# LASERTAG.net
KiCad netlist of a schematic drawn in EAGLE
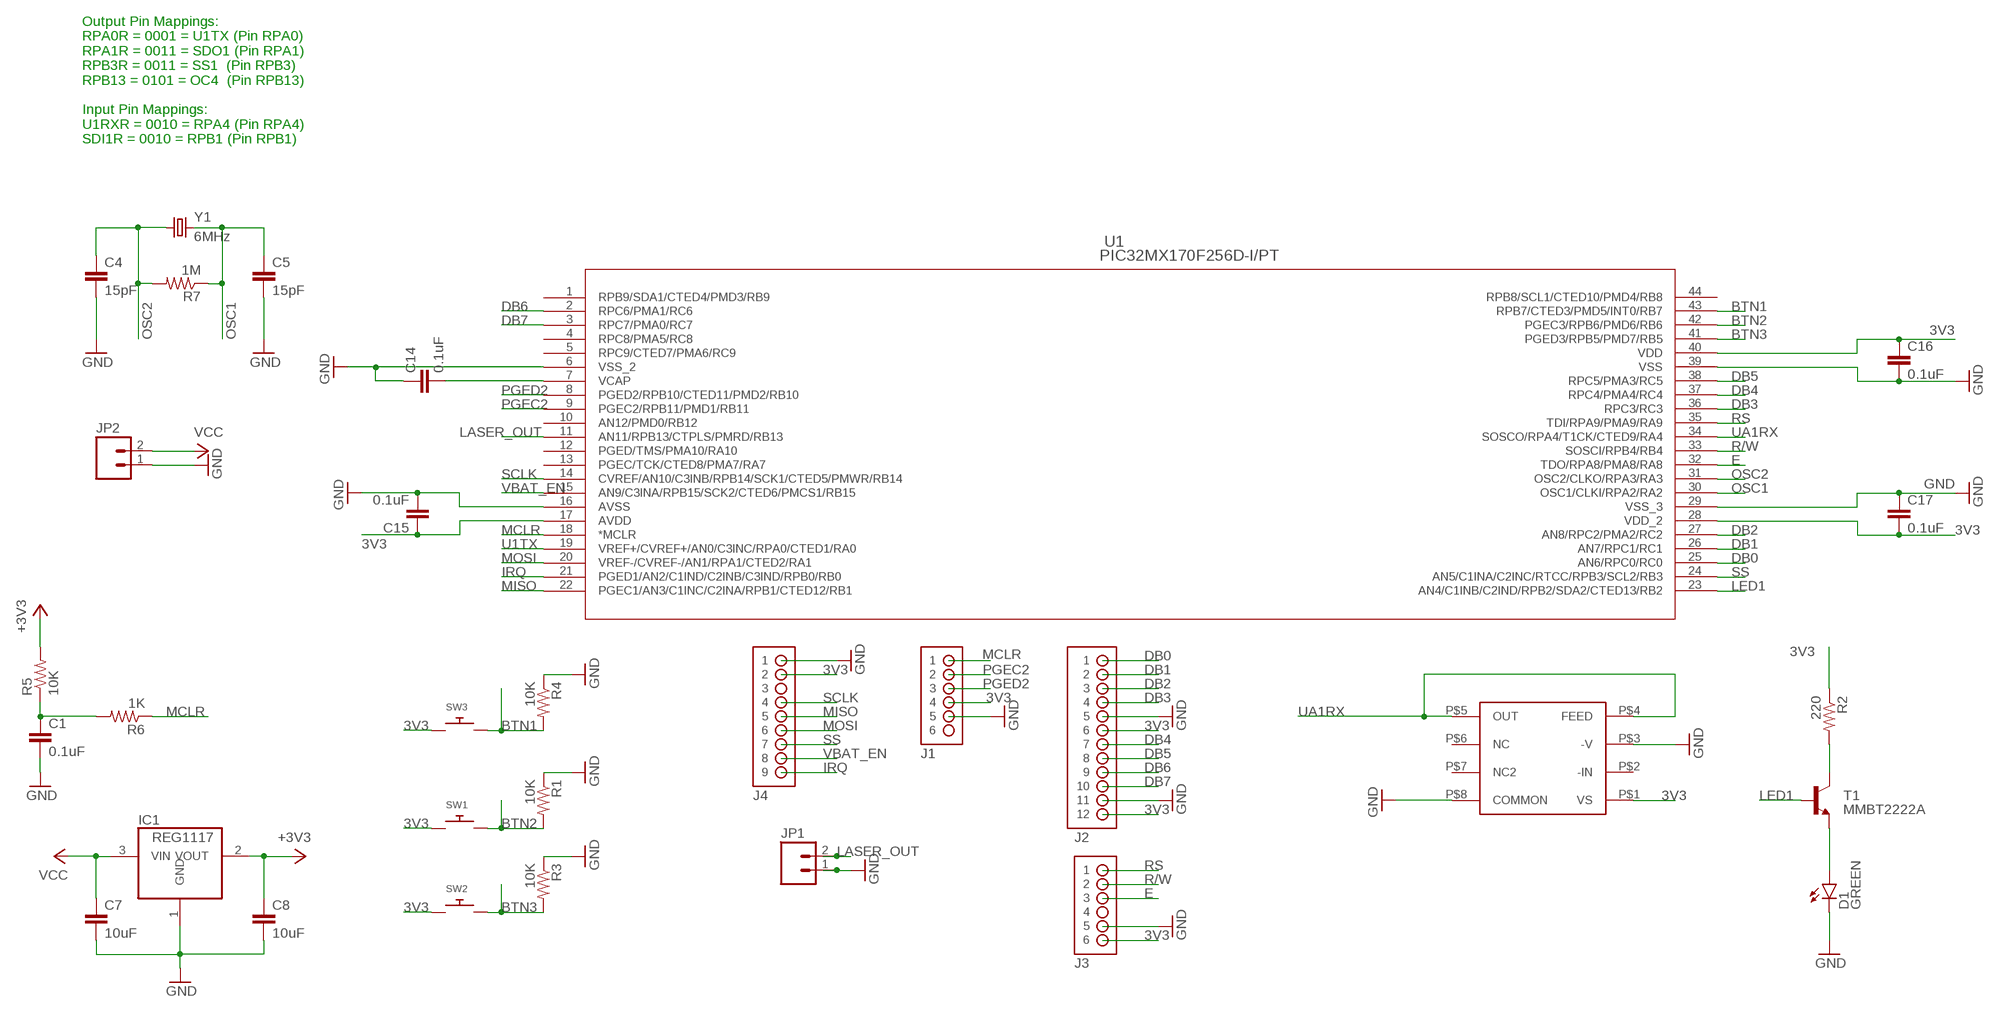
[diagram p0: schematic, sheet 1]

(export (version "E")
  (design (tool "Eeschema 10.0.6"))
  (components
    (comp (ref "C1")
      (value "0.1uF")
      (footprint "eagle-import:0603-CAP")
      (libsource (lib "eagle-import") (part "CAP0603-CAP"))
    )
    (comp (ref "C4")
      (value "15pF")
      (footprint "eagle-import:0603-CAP")
      (libsource (lib "eagle-import") (part "15PF-50V-5%(0603)"))
    )
    (comp (ref "C5")
      (value "15pF")
      (footprint "eagle-import:0603-CAP")
      (libsource (lib "eagle-import") (part "15PF-50V-5%(0603)"))
    )
    (comp (ref "C7")
      (value "10uF")
      (footprint "eagle-import:0603-CAP")
      (libsource (lib "eagle-import") (part "10UF-6.3V-20%(0603)"))
    )
    (comp (ref "C8")
      (value "10uF")
      (footprint "eagle-import:0603-CAP")
      (libsource (lib "eagle-import") (part "10UF-6.3V-20%(0603)"))
    )
    (comp (ref "C14")
      (value "0.1uF")
      (footprint "eagle-import:0603-CAP")
      (libsource (lib "eagle-import") (part "CAP0603-CAP"))
    )
    (comp (ref "C15")
      (value "0.1uF")
      (footprint "eagle-import:0603-CAP")
      (libsource (lib "eagle-import") (part "CAP0603-CAP"))
    )
    (comp (ref "C16")
      (value "0.1uF")
      (footprint "eagle-import:0603-CAP")
      (libsource (lib "eagle-import") (part "CAP0603-CAP"))
    )
    (comp (ref "C17")
      (value "0.1uF")
      (footprint "eagle-import:0603-CAP")
      (libsource (lib "eagle-import") (part "CAP0603-CAP"))
    )
    (comp (ref "D1")
      (value "GREEN")
      (footprint "eagle-import:LED-0603")
      (libsource (lib "eagle-import") (part "LED-GREEN0603"))
    )
    (comp (ref "IC1")
      (value "REG1117")
      (footprint "eagle-import:SOT223")
      (libsource (lib "eagle-import") (part "REG1117"))
    )
    (comp (ref "IC3")
      (value "OPT101P")
      (footprint "eagle-import:OPT101P")
      (libsource (lib "eagle-import") (part "OPT101P"))
    )
    (comp (ref "J1")
      (value "HDR-1X6")
      (footprint "eagle-import:HDR-1X6")
      (libsource (lib "eagle-import") (part "HDR-1X6"))
    )
    (comp (ref "J2")
      (value "PMOD-2X6-P")
      (footprint "eagle-import:PMOD-2X6-P")
      (libsource (lib "eagle-import") (part "PMOD-2X6-P"))
    )
    (comp (ref "J3")
      (value "HDR-1X6")
      (footprint "eagle-import:HDR-1X6")
      (libsource (lib "eagle-import") (part "HDR-1X6"))
    )
    (comp (ref "J4")
      (value "HDR-1X9")
      (footprint "eagle-import:HDR-1X9")
      (libsource (lib "eagle-import") (part "HDR-1X9"))
    )
    (comp (ref "JP1")
      (value "M02JST-PTH-2")
      (footprint "eagle-import:JST-2-PTH")
      (libsource (lib "eagle-import") (part "M02JST-PTH-2"))
    )
    (comp (ref "JP2")
      (value "M02JST-PTH-2")
      (footprint "eagle-import:JST-2-PTH")
      (libsource (lib "eagle-import") (part "M02JST-PTH-2"))
    )
    (comp (ref "R1")
      (value "10K")
      (footprint "eagle-import:0603-RES")
      (libsource (lib "eagle-import") (part "RESISTOR0603-RES"))
    )
    (comp (ref "R2")
      (value "220")
      (footprint "eagle-import:0603-RES")
      (libsource (lib "eagle-import") (part "RESISTOR0603-RES"))
    )
    (comp (ref "R3")
      (value "10K")
      (footprint "eagle-import:0603-RES")
      (libsource (lib "eagle-import") (part "RESISTOR0603-RES"))
    )
    (comp (ref "R4")
      (value "10K")
      (footprint "eagle-import:0603-RES")
      (libsource (lib "eagle-import") (part "RESISTOR0603-RES"))
    )
    (comp (ref "R5")
      (value "10K")
      (footprint "eagle-import:0603-RES")
      (libsource (lib "eagle-import") (part "RESISTOR0603-RES"))
    )
    (comp (ref "R6")
      (value "1K")
      (footprint "eagle-import:0603-RES")
      (libsource (lib "eagle-import") (part "RESISTOR0603-RES"))
    )
    (comp (ref "R7")
      (value "1M")
      (footprint "eagle-import:0603-RES")
      (libsource (lib "eagle-import") (part "1MOHM-1/10W-1%(0603)"))
    )
    (comp (ref "SW1")
      (value "SWITCH_PUSHBUTTONC&K_KSS")
      (footprint "eagle-import:BTN_CK_KSS")
      (libsource (lib "eagle-import") (part "SWITCH_PUSHBUTTONC&K_KSS"))
    )
    (comp (ref "SW2")
      (value "SWITCH_PUSHBUTTONC&K_KSS")
      (footprint "eagle-import:BTN_CK_KSS")
      (libsource (lib "eagle-import") (part "SWITCH_PUSHBUTTONC&K_KSS"))
    )
    (comp (ref "SW3")
      (value "SWITCH_PUSHBUTTONC&K_KSS")
      (footprint "eagle-import:BTN_CK_KSS")
      (libsource (lib "eagle-import") (part "SWITCH_PUSHBUTTONC&K_KSS"))
    )
    (comp (ref "T1")
      (value "MMBT2222A")
      (footprint "eagle-import:SOT23")
      (libsource (lib "eagle-import") (part "TRANSISTOR_NPNSOT23"))
    )
    (comp (ref "U1")
      (value "PIC32MX170F256D-I/PT")
      (footprint "eagle-import:TQFP44_10X10MC")
      (libsource (lib "eagle-import") (part "PIC32MX150F128D-I_PT"))
    )
    (comp (ref "Y1")
      (value "6MHz")
      (footprint "eagle-import:HC49US")
      (libsource (lib "eagle-import") (part "CRYSTALHC49US"))
    )
  )
  (nets
    (net (code "1") (name "+3V3") (class "Default")
      (node (ref "C15") (pin "1") (pinfunction "1_1") (pintype "passive"))
      (node (ref "C16") (pin "1") (pinfunction "1_1") (pintype "passive"))
      (node (ref "C17") (pin "2") (pinfunction "2_2") (pintype "passive"))
      (node (ref "C8") (pin "1") (pinfunction "1_1") (pintype "passive"))
      (node (ref "IC1") (pin "2") (pinfunction "VOUT_2") (pintype "power_in"))
      (node (ref "IC3") (pin "P$1") (pinfunction "VS_P$1") (pintype "bidirectional"))
      (node (ref "J1") (pin "4") (pinfunction "4_4") (pintype "passive"))
      (node (ref "J2") (pin "12") (pinfunction "12_12") (pintype "passive"))
      (node (ref "J2") (pin "6") (pinfunction "6_6") (pintype "passive"))
      (node (ref "J3") (pin "6") (pinfunction "6_6") (pintype "passive"))
      (node (ref "J4") (pin "2") (pinfunction "2_2") (pintype "passive"))
      (node (ref "R2") (pin "1") (pinfunction "1_1") (pintype "passive"))
      (node (ref "R5") (pin "2") (pinfunction "2_2") (pintype "passive"))
      (node (ref "SW1") (pin "P$1") (pinfunction "P$1_P$1") (pintype "passive"))
      (node (ref "SW2") (pin "P$1") (pinfunction "P$1_P$1") (pintype "passive"))
      (node (ref "SW3") (pin "P$1") (pinfunction "P$1_P$1") (pintype "passive"))
      (node (ref "U1") (pin "17") (pinfunction "AVDD_17") (pintype "power_in"))
      (node (ref "U1") (pin "28") (pinfunction "VDD_2_28") (pintype "power_in"))
      (node (ref "U1") (pin "40") (pinfunction "VDD_40") (pintype "power_in"))
    )
    (net (code "2") (name "/BTN1") (class "Default")
      (node (ref "R4") (pin "2") (pinfunction "2_2") (pintype "passive"))
      (node (ref "SW3") (pin "P$2") (pinfunction "P$2_P$2") (pintype "passive"))
      (node (ref "U1") (pin "43") (pinfunction "RPB7/CTED3/PMD5/INT0/RB7_43") (pintype "bidirectional"))
    )
    (net (code "3") (name "/BTN2") (class "Default")
      (node (ref "R1") (pin "2") (pinfunction "2_2") (pintype "passive"))
      (node (ref "SW1") (pin "P$2") (pinfunction "P$2_P$2") (pintype "passive"))
      (node (ref "U1") (pin "42") (pinfunction "PGEC3/RPB6/PMD6/RB6_42") (pintype "bidirectional"))
    )
    (net (code "4") (name "/BTN3") (class "Default")
      (node (ref "R3") (pin "2") (pinfunction "2_2") (pintype "passive"))
      (node (ref "SW2") (pin "P$2") (pinfunction "P$2_P$2") (pintype "passive"))
      (node (ref "U1") (pin "41") (pinfunction "PGED3/RPB5/PMD7/RB5_41") (pintype "bidirectional"))
    )
    (net (code "5") (name "/DB0") (class "Default")
      (node (ref "J2") (pin "1") (pinfunction "1_1") (pintype "passive"))
      (node (ref "U1") (pin "25") (pinfunction "AN6/RPC0/RC0_25") (pintype "bidirectional"))
    )
    (net (code "6") (name "/DB1") (class "Default")
      (node (ref "J2") (pin "2") (pinfunction "2_2") (pintype "passive"))
      (node (ref "U1") (pin "26") (pinfunction "AN7/RPC1/RC1_26") (pintype "bidirectional"))
    )
    (net (code "7") (name "/DB2") (class "Default")
      (node (ref "J2") (pin "3") (pinfunction "3_3") (pintype "passive"))
      (node (ref "U1") (pin "27") (pinfunction "AN8/RPC2/PMA2/RC2_27") (pintype "bidirectional"))
    )
    (net (code "8") (name "/DB3") (class "Default")
      (node (ref "J2") (pin "4") (pinfunction "4_4") (pintype "passive"))
      (node (ref "U1") (pin "36") (pinfunction "RPC3/RC3_36") (pintype "bidirectional"))
    )
    (net (code "9") (name "/DB4") (class "Default")
      (node (ref "J2") (pin "7") (pinfunction "7_7") (pintype "passive"))
      (node (ref "U1") (pin "37") (pinfunction "RPC4/PMA4/RC4_37") (pintype "bidirectional"))
    )
    (net (code "10") (name "/DB5") (class "Default")
      (node (ref "J2") (pin "8") (pinfunction "8_8") (pintype "passive"))
      (node (ref "U1") (pin "38") (pinfunction "RPC5/PMA3/RC5_38") (pintype "bidirectional"))
    )
    (net (code "11") (name "/DB6") (class "Default")
      (node (ref "J2") (pin "9") (pinfunction "9_9") (pintype "passive"))
      (node (ref "U1") (pin "2") (pinfunction "RPC6/PMA1/RC6_2") (pintype "bidirectional"))
    )
    (net (code "12") (name "/DB7") (class "Default")
      (node (ref "J2") (pin "10") (pinfunction "10_10") (pintype "passive"))
      (node (ref "U1") (pin "3") (pinfunction "RPC7/PMA0/RC7_3") (pintype "bidirectional"))
    )
    (net (code "13") (name "/E") (class "Default")
      (node (ref "J3") (pin "3") (pinfunction "3_3") (pintype "passive"))
      (node (ref "U1") (pin "32") (pinfunction "TDO/RPA8/PMA8/RA8_32") (pintype "bidirectional"))
    )
    (net (code "14") (name "/IRQ") (class "Default")
      (node (ref "J4") (pin "9") (pinfunction "9_9") (pintype "passive"))
      (node (ref "U1") (pin "21") (pinfunction "PGED1/AN2/C1IND/C2INB/C3IND/RPB0/RB0_21") (pintype "bidirectional"))
    )
    (net (code "15") (name "/LASER_OUT") (class "Default")
      (node (ref "JP1") (pin "2") (pinfunction "2_2") (pintype "passive"))
      (node (ref "U1") (pin "11") (pinfunction "AN11/RPB13/CTPLS/PMRD/RB13_11") (pintype "bidirectional"))
    )
    (net (code "16") (name "/LED1") (class "Default")
      (node (ref "T1") (pin "1") (pinfunction "B_1") (pintype "passive"))
      (node (ref "U1") (pin "23") (pinfunction "AN4/C1INB/C2IND/RPB2/SDA2/CTED13/RB2_23") (pintype "bidirectional"))
    )
    (net (code "17") (name "/MCLR") (class "Default")
      (node (ref "J1") (pin "1") (pinfunction "1_1") (pintype "passive"))
      (node (ref "R6") (pin "1") (pinfunction "1_1") (pintype "passive"))
      (node (ref "U1") (pin "18") (pinfunction "*MCLR_18") (pintype "input"))
    )
    (net (code "18") (name "/MISO") (class "Default")
      (node (ref "J4") (pin "5") (pinfunction "5_5") (pintype "passive"))
      (node (ref "U1") (pin "22") (pinfunction "PGEC1/AN3/C1INC/C2INA/RPB1/CTED12/RB1_22") (pintype "bidirectional"))
    )
    (net (code "19") (name "/MOSI") (class "Default")
      (node (ref "J4") (pin "6") (pinfunction "6_6") (pintype "passive"))
      (node (ref "U1") (pin "20") (pinfunction "VREF-/CVREF-/AN1/RPA1/CTED2/RA1_20") (pintype "bidirectional"))
    )
    (net (code "20") (name "/OSC1") (class "Default")
      (node (ref "C5") (pin "1") (pinfunction "1_1") (pintype "passive"))
      (node (ref "R7") (pin "1") (pinfunction "1_1") (pintype "passive"))
      (node (ref "U1") (pin "30") (pinfunction "OSC1/CLKI/RPA2/RA2_30") (pintype "bidirectional"))
      (node (ref "Y1") (pin "2") (pinfunction "2_2") (pintype "passive"))
    )
    (net (code "21") (name "/OSC2") (class "Default")
      (node (ref "C4") (pin "1") (pinfunction "1_1") (pintype "passive"))
      (node (ref "R7") (pin "2") (pinfunction "2_2") (pintype "passive"))
      (node (ref "U1") (pin "31") (pinfunction "OSC2/CLKO/RPA3/RA3_31") (pintype "bidirectional"))
      (node (ref "Y1") (pin "1") (pinfunction "1_1") (pintype "passive"))
    )
    (net (code "22") (name "/PGEC2") (class "Default")
      (node (ref "J1") (pin "2") (pinfunction "2_2") (pintype "passive"))
      (node (ref "U1") (pin "9") (pinfunction "PGEC2/RPB11/PMD1/RB11_9") (pintype "bidirectional"))
    )
    (net (code "23") (name "/PGED2") (class "Default")
      (node (ref "J1") (pin "3") (pinfunction "3_3") (pintype "passive"))
      (node (ref "U1") (pin "8") (pinfunction "PGED2/RPB10/CTED11/PMD2/RB10_8") (pintype "bidirectional"))
    )
    (net (code "24") (name "/RS") (class "Default")
      (node (ref "J3") (pin "1") (pinfunction "1_1") (pintype "passive"))
      (node (ref "U1") (pin "35") (pinfunction "TDI/RPA9/PMA9/RA9_35") (pintype "bidirectional"))
    )
    (net (code "25") (name "/R{slash}W") (class "Default")
      (node (ref "J3") (pin "2") (pinfunction "2_2") (pintype "passive"))
      (node (ref "U1") (pin "33") (pinfunction "SOSCI/RPB4/RB4_33") (pintype "bidirectional"))
    )
    (net (code "26") (name "/SCLK") (class "Default")
      (node (ref "J4") (pin "4") (pinfunction "4_4") (pintype "passive"))
      (node (ref "U1") (pin "14") (pinfunction "CVREF/AN10/C3INB/RPB14/SCK1/CTED5/PMWR/RB14_14") (pintype "bidirectional"))
    )
    (net (code "27") (name "/SS") (class "Default")
      (node (ref "J4") (pin "7") (pinfunction "7_7") (pintype "passive"))
      (node (ref "U1") (pin "24") (pinfunction "AN5/C1INA/C2INC/RTCC/RPB3/SCL2/RB3_24") (pintype "bidirectional"))
    )
    (net (code "28") (name "/U1TX") (class "Default")
      (node (ref "U1") (pin "19") (pinfunction "VREF+/CVREF+/AN0/C3INC/RPA0/CTED1/RA0_19") (pintype "bidirectional"))
    )
    (net (code "29") (name "/UA1RX") (class "Default")
      (node (ref "IC3") (pin "P$4") (pinfunction "FEED_P$4") (pintype "bidirectional"))
      (node (ref "IC3") (pin "P$5") (pinfunction "OUT_P$5") (pintype "bidirectional"))
      (node (ref "U1") (pin "34") (pinfunction "SOSCO/RPA4/T1CK/CTED9/RA4_34") (pintype "bidirectional"))
    )
    (net (code "30") (name "/VBAT_EN") (class "Default")
      (node (ref "J4") (pin "8") (pinfunction "8_8") (pintype "passive"))
      (node (ref "U1") (pin "15") (pinfunction "AN9/C3INA/RPB15/SCK2/CTED6/PMCS1/RB15_15") (pintype "bidirectional"))
    )
    (net (code "31") (name "GND") (class "Default")
      (node (ref "C1") (pin "2") (pinfunction "2_2") (pintype "passive"))
      (node (ref "C14") (pin "1") (pinfunction "1_1") (pintype "passive"))
      (node (ref "C15") (pin "2") (pinfunction "2_2") (pintype "passive"))
      (node (ref "C16") (pin "2") (pinfunction "2_2") (pintype "passive"))
      (node (ref "C17") (pin "1") (pinfunction "1_1") (pintype "passive"))
      (node (ref "C4") (pin "2") (pinfunction "2_2") (pintype "passive"))
      (node (ref "C5") (pin "2") (pinfunction "2_2") (pintype "passive"))
      (node (ref "C7") (pin "2") (pinfunction "2_2") (pintype "passive"))
      (node (ref "C8") (pin "2") (pinfunction "2_2") (pintype "passive"))
      (node (ref "D1") (pin "C") (pinfunction "C_C") (pintype "passive"))
      (node (ref "IC1") (pin "1") (pinfunction "GND_1") (pintype "power_in"))
      (node (ref "IC3") (pin "P$3") (pinfunction "-V_P$3") (pintype "bidirectional"))
      (node (ref "IC3") (pin "P$8") (pinfunction "COMMON_P$8") (pintype "bidirectional"))
      (node (ref "J1") (pin "5") (pinfunction "5_5") (pintype "passive"))
      (node (ref "J2") (pin "11") (pinfunction "11_11") (pintype "passive"))
      (node (ref "J2") (pin "5") (pinfunction "5_5") (pintype "passive"))
      (node (ref "J3") (pin "5") (pinfunction "5_5") (pintype "passive"))
      (node (ref "J4") (pin "1") (pinfunction "1_1") (pintype "passive"))
      (node (ref "JP1") (pin "1") (pinfunction "1_1") (pintype "passive"))
      (node (ref "JP2") (pin "1") (pinfunction "1_1") (pintype "passive"))
      (node (ref "R1") (pin "1") (pinfunction "1_1") (pintype "passive"))
      (node (ref "R3") (pin "1") (pinfunction "1_1") (pintype "passive"))
      (node (ref "R4") (pin "1") (pinfunction "1_1") (pintype "passive"))
      (node (ref "U1") (pin "16") (pinfunction "AVSS_16") (pintype "power_in"))
      (node (ref "U1") (pin "29") (pinfunction "VSS_3_29") (pintype "power_in"))
      (node (ref "U1") (pin "39") (pinfunction "VSS_39") (pintype "power_in"))
      (node (ref "U1") (pin "6") (pinfunction "VSS_2_6") (pintype "power_in"))
    )
    (net (code "32") (name "Net-(C1-Pad1)") (class "Default")
      (node (ref "C1") (pin "1") (pinfunction "1_1") (pintype "passive"))
      (node (ref "R5") (pin "1") (pinfunction "1_1") (pintype "passive"))
      (node (ref "R6") (pin "2") (pinfunction "2_2") (pintype "passive"))
    )
    (net (code "33") (name "Net-(T1-C)") (class "Default")
      (node (ref "R2") (pin "2") (pinfunction "2_2") (pintype "passive"))
      (node (ref "T1") (pin "3") (pinfunction "C_3") (pintype "passive"))
    )
    (net (code "34") (name "Net-(T1-E)") (class "Default")
      (node (ref "D1") (pin "A") (pinfunction "A_A") (pintype "passive"))
      (node (ref "T1") (pin "2") (pinfunction "E_2") (pintype "passive"))
    )
    (net (code "35") (name "Net-(U1-VCAP)") (class "Default")
      (node (ref "C14") (pin "2") (pinfunction "2_2") (pintype "passive"))
      (node (ref "U1") (pin "7") (pinfunction "VCAP_7") (pintype "power_in"))
    )
    (net (code "36") (name "VCC") (class "Default")
      (node (ref "C7") (pin "1") (pinfunction "1_1") (pintype "passive"))
      (node (ref "IC1") (pin "3") (pinfunction "VIN_3") (pintype "input"))
      (node (ref "JP2") (pin "2") (pinfunction "2_2") (pintype "passive"))
    )
    (net (code "37") (name "unconnected-(IC3--IN-PadP$2)") (class "Default")
      (node (ref "IC3") (pin "P$2") (pinfunction "-IN_P$2") (pintype "bidirectional"))
    )
    (net (code "38") (name "unconnected-(IC3-NC-PadP$6)") (class "Default")
      (node (ref "IC3") (pin "P$6") (pinfunction "NC_P$6") (pintype "bidirectional"))
    )
    (net (code "39") (name "unconnected-(IC3-NC2-PadP$7)") (class "Default")
      (node (ref "IC3") (pin "P$7") (pinfunction "NC2_P$7") (pintype "bidirectional"))
    )
    (net (code "40") (name "unconnected-(J1-Pad6)") (class "Default")
      (node (ref "J1") (pin "6") (pinfunction "6_6") (pintype "passive"))
    )
    (net (code "41") (name "unconnected-(J3-Pad4)") (class "Default")
      (node (ref "J3") (pin "4") (pinfunction "4_4") (pintype "passive"))
    )
    (net (code "42") (name "unconnected-(J4-Pad3)") (class "Default")
      (node (ref "J4") (pin "3") (pinfunction "3_3") (pintype "passive"))
    )
    (net (code "43") (name "unconnected-(U1-AN12{slash}PMD0{slash}RB12-Pad10)") (class "Default")
      (node (ref "U1") (pin "10") (pinfunction "AN12/PMD0/RB12_10") (pintype "bidirectional"))
    )
    (net (code "44") (name "unconnected-(U1-PGEC{slash}TCK{slash}CTED8{slash}PMA7{slash}RA7-Pad13)") (class "Default")
      (node (ref "U1") (pin "13") (pinfunction "PGEC/TCK/CTED8/PMA7/RA7_13") (pintype "bidirectional"))
    )
    (net (code "45") (name "unconnected-(U1-PGED{slash}TMS{slash}PMA10{slash}RA10-Pad12)") (class "Default")
      (node (ref "U1") (pin "12") (pinfunction "PGED/TMS/PMA10/RA10_12") (pintype "bidirectional"))
    )
    (net (code "46") (name "unconnected-(U1-RPB8{slash}SCL1{slash}CTED10{slash}PMD4{slash}RB8-Pad44)") (class "Default")
      (node (ref "U1") (pin "44") (pinfunction "RPB8/SCL1/CTED10/PMD4/RB8_44") (pintype "bidirectional"))
    )
    (net (code "47") (name "unconnected-(U1-RPB9{slash}SDA1{slash}CTED4{slash}PMD3{slash}RB9-Pad1)") (class "Default")
      (node (ref "U1") (pin "1") (pinfunction "RPB9/SDA1/CTED4/PMD3/RB9_1") (pintype "bidirectional"))
    )
    (net (code "48") (name "unconnected-(U1-RPC8{slash}PMA5{slash}RC8-Pad4)") (class "Default")
      (node (ref "U1") (pin "4") (pinfunction "RPC8/PMA5/RC8_4") (pintype "bidirectional"))
    )
    (net (code "49") (name "unconnected-(U1-RPC9{slash}CTED7{slash}PMA6{slash}RC9-Pad5)") (class "Default")
      (node (ref "U1") (pin "5") (pinfunction "RPC9/CTED7/PMA6/RC9_5") (pintype "bidirectional"))
    )
  )
)
